# H0FR60.net
KiCad netlist of a schematic drawn in EAGLE
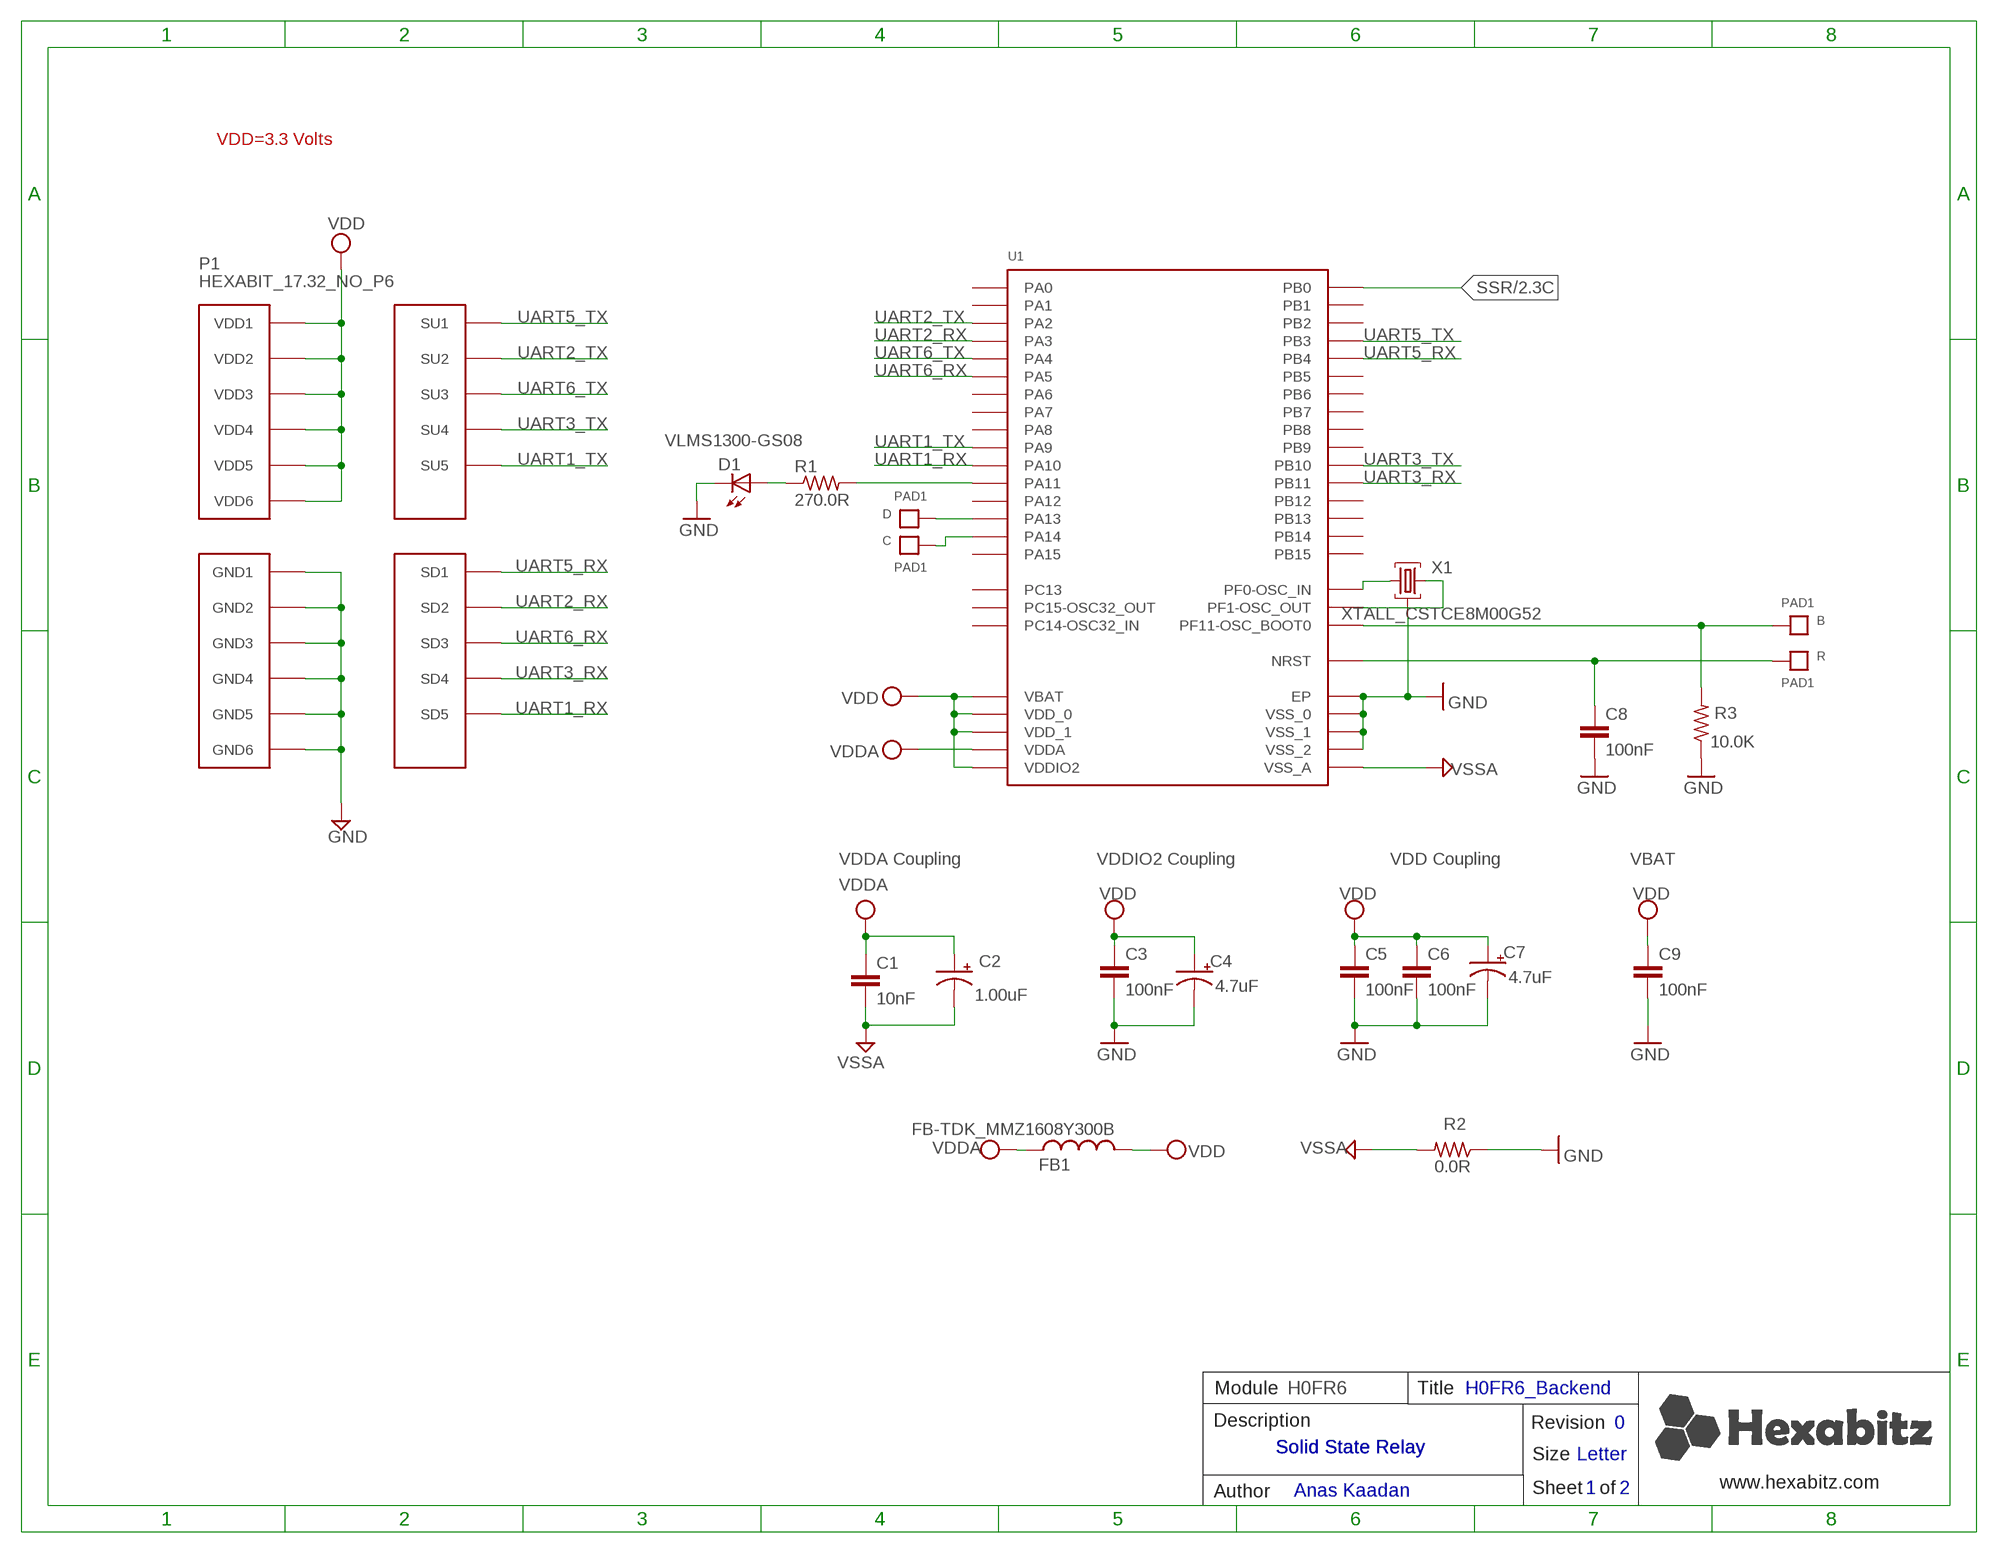
[diagram p0: schematic, sheet 1]
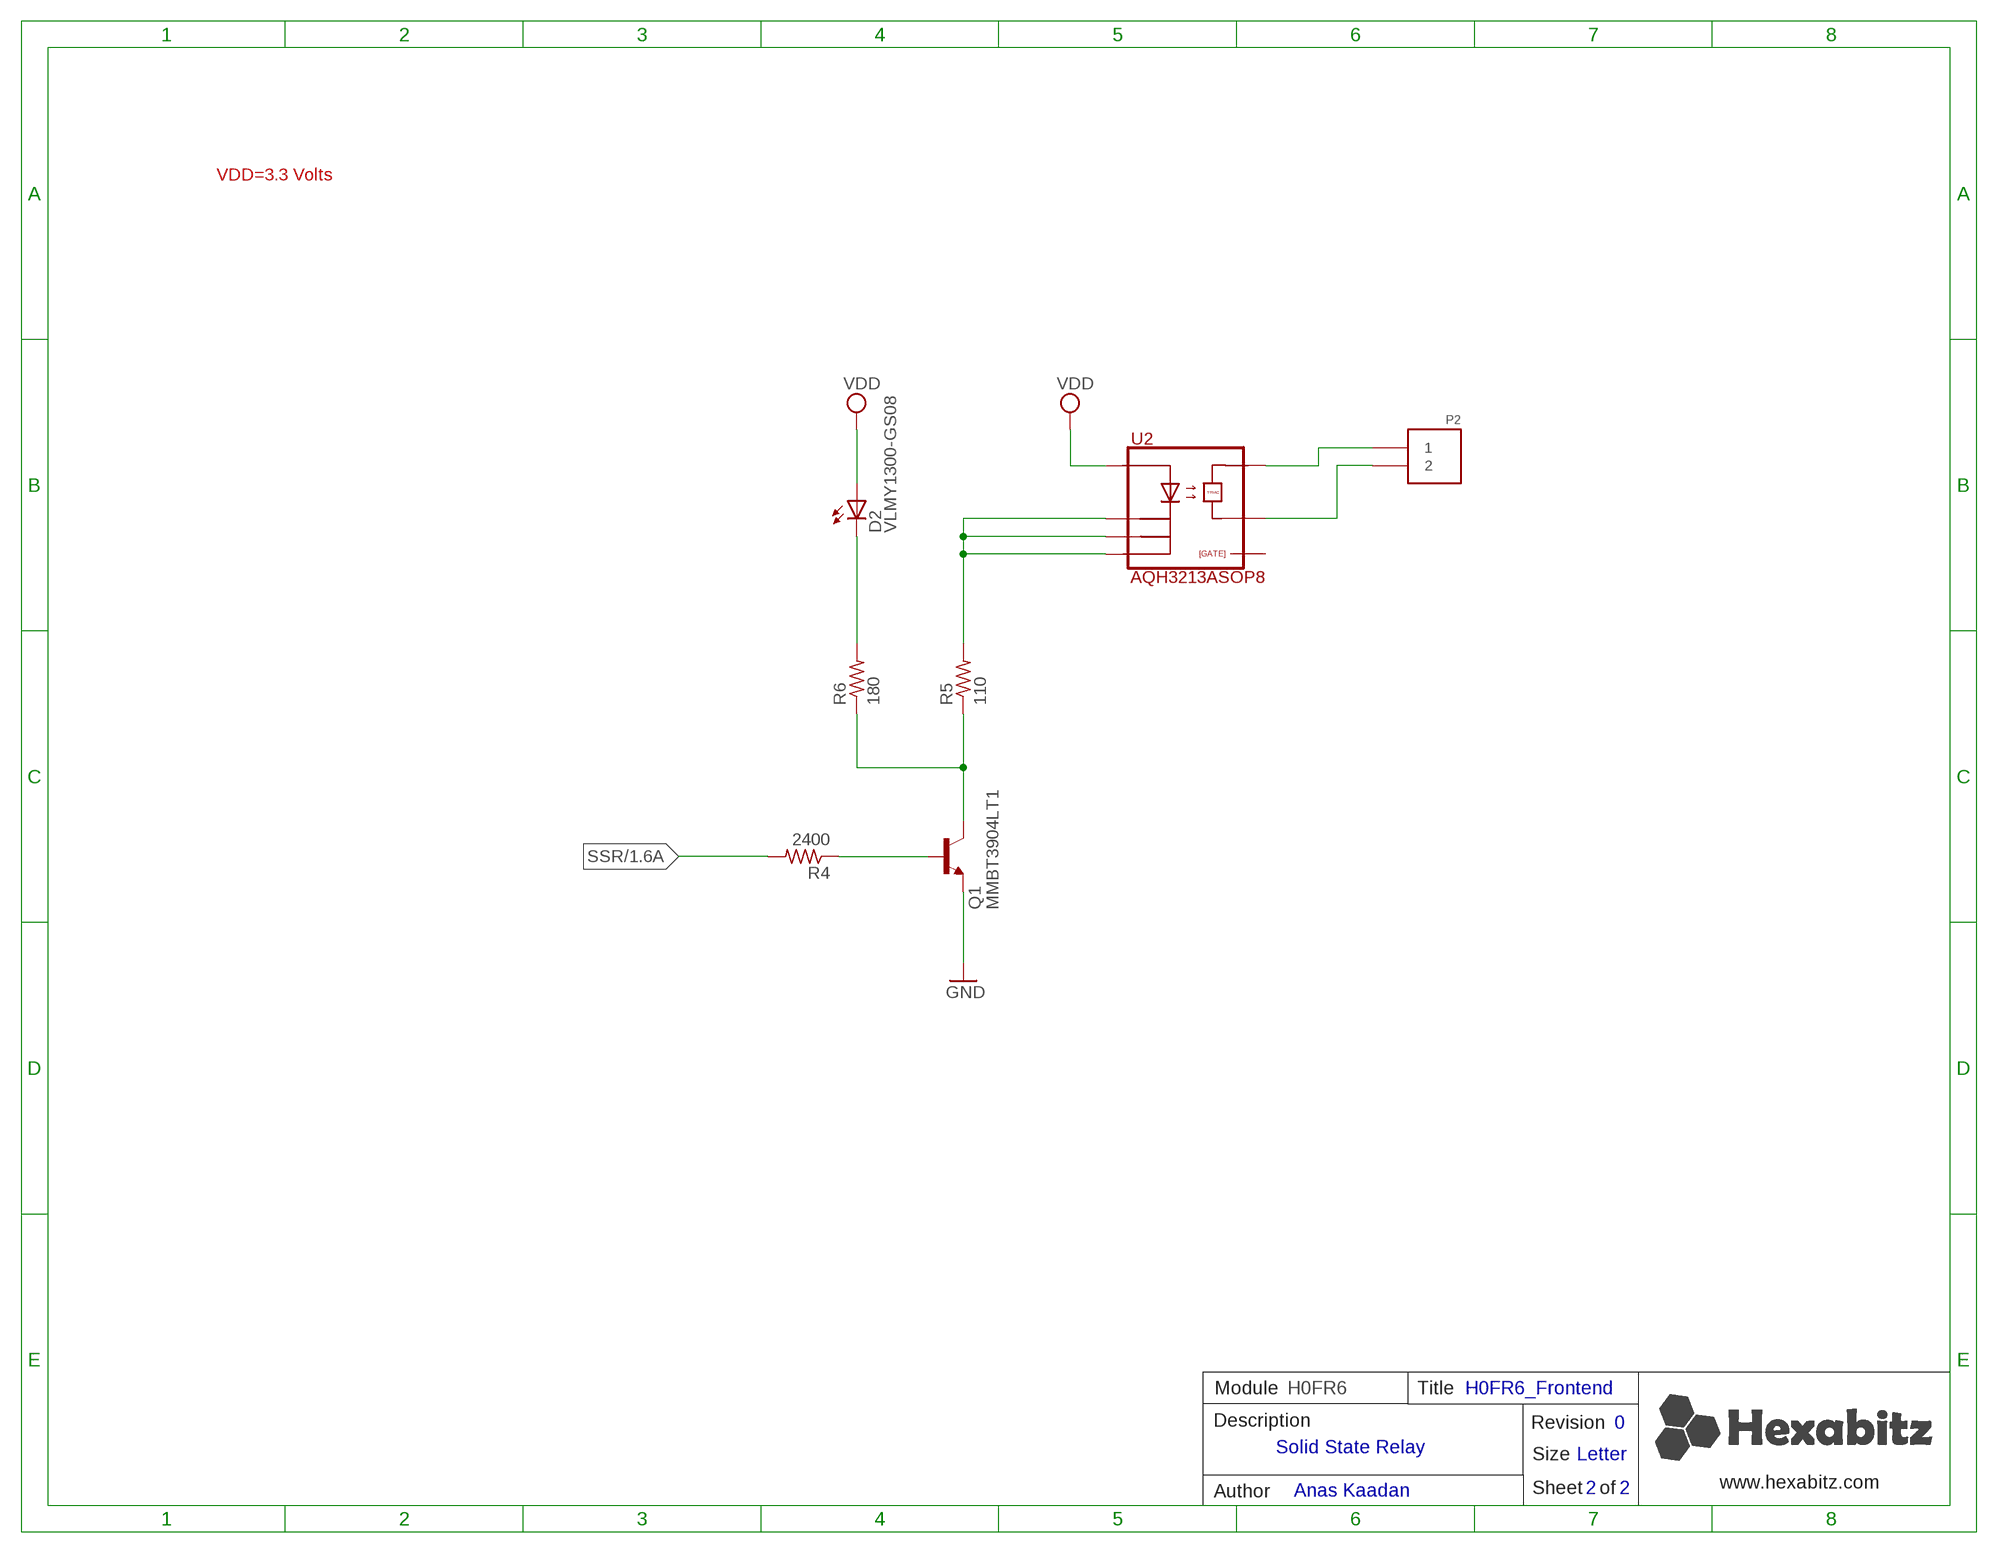
[diagram p1: schematic, sheet 2]

(export (version "E")
  (design (tool "Eeschema 10.0.6"))
  (components
    (comp (ref "B")
      (value "PAD1")
      (footprint "eagle-import:PAD1")
      (libsource (lib "eagle-import") (part "PAD1"))
    )
    (comp (ref "C")
      (value "PAD1")
      (footprint "eagle-import:PAD1")
      (libsource (lib "eagle-import") (part "PAD1"))
    )
    (comp (ref "C1")
      (value "10nF")
      (footprint "eagle-import:C-0603")
      (fields
        (field (name "CAPACITANCE") "10nF")
        (field (name "MFN") "KEMET")
        (field (name "MPN") "C0603C103K5RACTU")
        (field (name "OCTOPART_URL") "https://octopart.com/c0603c103k5ractu-kemet-133094?r=sp&s=R_iPBxLnSmGqhkU2rIMFpg")
        (field (name "TOLERANCE") "10%")
        (field (name "VOLTAGE_RATING") "50V")
      )
      (libsource (lib "eagle-import") (part "C-0603"))
    )
    (comp (ref "C2")
      (value "1.00uF")
      (footprint "eagle-import:C-0805-POL")
      (fields
        (field (name "CAPACITANCE") "1.00uF")
        (field (name "MFN") "Yageo")
        (field (name "MPN") "CC0805KKX7R7BB105")
        (field (name "OCTOPART_URL") "https://octopart.com/cc0805kkx7r7bb105-yageo-8376555?r=sp&s=YKl1wwtkROau_X5nniH2ig")
        (field (name "TOLERANCE") "10%")
        (field (name "VOLTAGE_RATING") "16V")
      )
      (libsource (lib "eagle-import") (part "C-0805-POL"))
    )
    (comp (ref "C3")
      (value "100nF")
      (footprint "eagle-import:C-0603")
      (fields
        (field (name "CAPACITANCE") "100nF")
        (field (name "MFN") "KEMET")
        (field (name "MPN") "C0603C104K8RACTU")
        (field (name "OCTOPART_URL") "https://octopart.com/c0603c104k8ractu-kemet-145075?r=sp&s=9bS9ASSwSEqMCE9KBEQZ0g")
        (field (name "TOLERANCE") "10%")
        (field (name "VOLTAGE_RATING") "10V")
      )
      (libsource (lib "eagle-import") (part "C-0603"))
    )
    (comp (ref "C4")
      (value "4.7uF")
      (footprint "eagle-import:C-0805-POL")
      (fields
        (field (name "CAPACITANCE") "4.7uF")
        (field (name "MFN") "Murata")
        (field (name "MPN") "GRM21BC81E475KA12L")
        (field (name "OCTOPART_URL") "https://octopart.com/grm21bc81e475ka12l-murata-10331911?r=sp&s=RY3qZSD8T6mG6TC9CHI5qQ")
        (field (name "TOLERANCE") "10%")
        (field (name "VOLTAGE_RATING") "25V")
      )
      (libsource (lib "eagle-import") (part "C-0805-POL"))
    )
    (comp (ref "C5")
      (value "100nF")
      (footprint "eagle-import:C-0603")
      (fields
        (field (name "CAPACITANCE") "100nF")
        (field (name "MFN") "KEMET")
        (field (name "MPN") "C0603C104K8RACTU")
        (field (name "OCTOPART_URL") "https://octopart.com/c0603c104k8ractu-kemet-145075?r=sp&s=9bS9ASSwSEqMCE9KBEQZ0g")
        (field (name "TOLERANCE") "10%")
        (field (name "VOLTAGE_RATING") "10")
      )
      (libsource (lib "eagle-import") (part "C-0603"))
    )
    (comp (ref "C6")
      (value "100nF")
      (footprint "eagle-import:C-0603")
      (fields
        (field (name "CAPACITANCE") "100nF")
        (field (name "MFN") "KEMET")
        (field (name "MPN") "C0603C104K8RACTU")
        (field (name "OCTOPART_URL") "https://octopart.com/c0603c104k8ractu-kemet-145075?r=sp&s=9bS9ASSwSEqMCE9KBEQZ0g")
        (field (name "TOLERANCE") "10%")
        (field (name "VOLTAGE_RATING") "10V")
      )
      (libsource (lib "eagle-import") (part "C-0603"))
    )
    (comp (ref "C7")
      (value "4.7uF")
      (footprint "eagle-import:C-0805-POL")
      (fields
        (field (name "CAPACITANCE") "4.7uF")
        (field (name "MFN") "Murata")
        (field (name "MPN") "GRM21BC81E475KA12L")
        (field (name "OCTOPART_URL") "https://octopart.com/grm21bc81e475ka12l-murata-10331911?r=sp&s=RY3qZSD8T6mG6TC9CHI5qQ")
        (field (name "TOLERANCE") "10%")
        (field (name "VOLTAGE_RATING") "25V")
      )
      (libsource (lib "eagle-import") (part "C-0805-POL"))
    )
    (comp (ref "C8")
      (value "100nF")
      (footprint "eagle-import:C-0603")
      (fields
        (field (name "CAPACITANCE") "100nF")
        (field (name "MFN") "KEMET")
        (field (name "MPN") "C0603C104K8RACTU")
        (field (name "OCTOPART_URL") "https://octopart.com/c0603c104k8ractu-kemet-145075?r=sp&s=9bS9ASSwSEqMCE9KBEQZ0g")
        (field (name "TOLERANCE") "10%")
        (field (name "VOLTAGE_RATING") "10V")
      )
      (libsource (lib "eagle-import") (part "C-0603"))
    )
    (comp (ref "C9")
      (value "100nF")
      (footprint "eagle-import:C-0603")
      (fields
        (field (name "CAPACITANCE") "100nF")
        (field (name "MFN") "KEMET")
        (field (name "MPN") "C0603C104K8RACTU")
        (field (name "OCTOPART_URL") "https://octopart.com/c0603c104k8ractu-kemet-145075?r=sp&s=9bS9ASSwSEqMCE9KBEQZ0g")
        (field (name "TOLERANCE") "10V")
        (field (name "VOLTAGE_RATING") "10%")
      )
      (libsource (lib "eagle-import") (part "C-0603"))
    )
    (comp (ref "D")
      (value "PAD1")
      (footprint "eagle-import:PAD1")
      (libsource (lib "eagle-import") (part "PAD1"))
    )
    (comp (ref "D1")
      (value "VLMS1300-GS08")
      (footprint "eagle-import:VLMS1300-GS08")
      (fields
        (field (name "MFN") "Vishay")
        (field (name "MPN") "VLMS1300-GS08")
        (field (name "OCTOPART_URL") "https://octopart.com/vlms1300-gs08-vishay-21709201?r=sp&s=_gcP4_q8T1SC6PJQPTQ9yA")
      )
      (libsource (lib "eagle-import") (part "VLMS1300-GS08"))
    )
    (comp (ref "FB1")
      (value "FB-TDK_MMZ1608Y300B")
      (footprint "eagle-import:FB-TDK_MMZ1608Y300B")
      (fields
        (field (name "MFN") "TDK ")
        (field (name "MPN") "MMZ1608Y300B")
        (field (name "OCTOPART_URL") "https://octopart.com/mmz1608y300b-tdk-368280?r=sp&s=cd9_2ZEqQ9q9UNBuQgHAiA")
      )
      (libsource (lib "eagle-import") (part "FB-TDK_MMZ1608Y300B"))
    )
    (comp (ref "P1")
      (value "HEXABIT_17.32_NO_P6")
      (footprint "eagle-import:HEXABIT_17.32_NO_P6")
      (libsource (lib "eagle-import") (part "HEXABIT_?_NO_P617.32"))
    )
    (comp (ref "R")
      (value "PAD1")
      (footprint "eagle-import:PAD1")
      (libsource (lib "eagle-import") (part "PAD1"))
    )
    (comp (ref "R1")
      (value "270.0R")
      (footprint "eagle-import:R-0603")
      (fields
        (field (name "MFN") "Yageo")
        (field (name "MPN") "RC0603FR-07270RL")
        (field (name "OCTOPART_URL") "https://octopart.com/search?q=RC0603FR-07270RL&start=0")
        (field (name "RESISTANCE") "270.0 Ohm")
        (field (name "TOLERANCE") "1%")
      )
      (libsource (lib "eagle-import") (part "R-0603"))
    )
    (comp (ref "R2")
      (value "0.0R")
      (footprint "eagle-import:R-0603")
      (fields
        (field (name "MFN") "Yageo")
        (field (name "MPN") "RC0603JR-070RL")
        (field (name "OCTOPART_URL") "https://octopart.com/rc0603jr-070rl-yageo-1241539?r=sp&s=X2NteqRjRNWrnx42Y0aliA")
        (field (name "RESISTANCE") "0.0 Ohm")
      )
      (libsource (lib "eagle-import") (part "R-0603"))
    )
    (comp (ref "R3")
      (value "10.0K")
      (footprint "eagle-import:R-0603")
      (fields
        (field (name "MFN") "Yageo")
        (field (name "MPN") "RC0603JR-0710KL")
        (field (name "OCTOPART_URL") "https://octopart.com/search?q=RC0603JR-0710KL&start=0")
        (field (name "RESISTANCE") "10.0K Ohm")
        (field (name "TOLERANCE") "5%")
      )
      (libsource (lib "eagle-import") (part "R-0603"))
    )
    (comp (ref "U1")
      (value "STM32F091CBU6")
      (footprint "eagle-import:STM32F091CBU6")
      (libsource (lib "eagle-import") (part "STM32F091CBU6"))
    )
    (comp (ref "X1")
      (value "XTALL_CSTCE8M00G52")
      (footprint "eagle-import:XTALL_CSTCE8M00G52")
      (fields (field (name "MPN") "CSTCE8M00G52Z-R0"))
      (libsource (lib "eagle-import") (part "XTALL_CSTCE8M00G52"))
    )
    (comp (ref "D2")
      (value "VLMY1300-GS08")
      (footprint "eagle-import:VLMS1300-GS08")
      (fields
        (field (name "MFN") "Vishay ")
        (field (name "MPN") "VLMY1300-GS08")
        (field (name "OCTOPART_URL") "https://octopart.com/vlmy1300-gs08-vishay-21709204")
      )
      (libsource (lib "eagle-import") (part "VLMS1300-GS08"))
    )
    (comp (ref "P2")
      (value "1546111-2")
      (footprint "eagle-import:1546111-2")
      (libsource (lib "eagle-import") (part "1546111-2"))
    )
    (comp (ref "Q1")
      (value "MMBT3904LT1")
      (footprint "eagle-import:MMBT3904LT1")
      (fields
        (field (name "MFN") "ON Semiconductor")
        (field (name "MPN") "MMBT3904LT1G")
        (field (name "OCTOPART_ID") "0bb6c2bc2200d471")
        (field (name "OCTOPART_URL") "http://octopart.com/mmbt3904lt1g-on+semiconductor-3280")
        (field (name "POLARITY") "NPN")
        (field (name "POWER_DISSIPATION") "0.225 W")
        (field (name "VOLTAGE_RATING_DC") "40.0 V")
      )
      (libsource (lib "eagle-import") (part "MMBT3904LT1"))
    )
    (comp (ref "R4")
      (value "2400")
      (footprint "eagle-import:R-0603")
      (fields
        (field (name "MFN") "Yageo")
        (field (name "MPN") "RC0603JR-070RL")
        (field (name "OCTOPART_URL") "https://octopart.com/crcw06032k40jnea-vishay-40298967")
        (field (name "RESISTANCE") "2400.0 Ω")
        (field (name "TOLERANCE") "±5%")
      )
      (libsource (lib "eagle-import") (part "R-0603"))
    )
    (comp (ref "R5")
      (value "110")
      (footprint "eagle-import:R-0603")
      (fields
        (field (name "MFN") "Yageo")
        (field (name "MPN") "RC0402FR-07100RL")
        (field (name "OCTOPART_URL") "https://octopart.com/crcw0603110rfkea-vishay-39455532")
        (field (name "RESISTANCE") "110.0 Ω")
        (field (name "TOLERANCE") "±1%")
      )
      (libsource (lib "eagle-import") (part "R-0603"))
    )
    (comp (ref "R6")
      (value "180")
      (footprint "eagle-import:R-0603")
      (fields
        (field (name "MFN") "Yageo")
        (field (name "MPN") "RC0402FR-07100RL")
        (field (name "OCTOPART_URL") "https://octopart.com/erj-3geyj181v-panasonic-55403673")
        (field (name "RESISTANCE") "180.0 Ω")
        (field (name "TOLERANCE") "±5%")
      )
      (libsource (lib "eagle-import") (part "R-0603"))
    )
    (comp (ref "U2")
      (value "AQH3213ASOP8")
      (footprint "eagle-import:AQH3213A")
      (fields
        (field (name "MFN") "Panasonic")
        (field (name "MPN") "AQH3213A")
        (field (name "OCTOPART_ID") "3c1df74ea8f7e3da")
        (field (name "OCTOPART_URL") "http://octopart.com/aqh3213a-panasonic-39432588")
        (field (name "OUTPUT_CURRENT") "1.2 A")
        (field (name "OUTPUT_VOLTAGE") "600.0 V")
      )
      (libsource (lib "eagle-import") (part "AQH3213ASOP8"))
    )
  )
  (nets
    (net (code "1") (name "GND") (class "Default")
      (node (ref "C3") (pin "2") (pinfunction "2_2") (pintype "passive"))
      (node (ref "C4") (pin "2") (pinfunction "-_2") (pintype "passive"))
      (node (ref "C5") (pin "2") (pinfunction "2_2") (pintype "passive"))
      (node (ref "C6") (pin "2") (pinfunction "2_2") (pintype "passive"))
      (node (ref "C7") (pin "2") (pinfunction "-_2") (pintype "passive"))
      (node (ref "C8") (pin "2") (pinfunction "2_2") (pintype "passive"))
      (node (ref "C9") (pin "2") (pinfunction "2_2") (pintype "passive"))
      (node (ref "D1") (pin "C") (pinfunction "C_C") (pintype "passive"))
      (node (ref "P1") (pin "PAD_PD10") (pinfunction "GND4_PAD_PD10") (pintype "power_in"))
      (node (ref "P1") (pin "PAD_PD11") (pinfunction "GND5_PAD_PD11") (pintype "power_in"))
      (node (ref "P1") (pin "PAD_PD12") (pinfunction "GND6_PAD_PD12") (pintype "power_in"))
      (node (ref "P1") (pin "PAD_PD7") (pinfunction "GND1_PAD_PD7") (pintype "power_in"))
      (node (ref "P1") (pin "PAD_PD8") (pinfunction "GND2_PAD_PD8") (pintype "power_in"))
      (node (ref "P1") (pin "PAD_PD9") (pinfunction "GND3_PAD_PD9") (pintype "power_in"))
      (node (ref "Q1") (pin "2") (pinfunction "E_2") (pintype "passive"))
      (node (ref "R2") (pin "1") (pinfunction "1_1") (pintype "passive"))
      (node (ref "R3") (pin "1") (pinfunction "1_1") (pintype "passive"))
      (node (ref "U1") (pin "EP") (pinfunction "EP_EP") (pintype "power_in"))
      (node (ref "U1") (pin "P$23") (pinfunction "VSS_0_P$23") (pintype "power_in"))
      (node (ref "U1") (pin "P$35") (pinfunction "VSS_1_P$35") (pintype "power_in"))
      (node (ref "U1") (pin "P$47") (pinfunction "VSS_2_P$47") (pintype "power_in"))
      (node (ref "X1") (pin "P$2") (pinfunction "2_P$2") (pintype "passive"))
    )
    (net (code "2") (name "Net-(D1-PadA)") (class "Default")
      (node (ref "D1") (pin "A") (pinfunction "A_A") (pintype "passive"))
      (node (ref "R1") (pin "1") (pinfunction "1_1") (pintype "passive"))
    )
    (net (code "3") (name "Net-(D2-PadC)") (class "Default")
      (node (ref "D2") (pin "C") (pinfunction "C_C") (pintype "passive"))
      (node (ref "R6") (pin "2") (pinfunction "2_2") (pintype "passive"))
    )
    (net (code "4") (name "Net-(Q1-B)") (class "Default")
      (node (ref "Q1") (pin "1") (pinfunction "B_1") (pintype "passive"))
      (node (ref "R4") (pin "1") (pinfunction "1_1") (pintype "passive"))
    )
    (net (code "5") (name "Net-(Q1-C)") (class "Default")
      (node (ref "Q1") (pin "3") (pinfunction "C_3") (pintype "passive"))
      (node (ref "R5") (pin "1") (pinfunction "1_1") (pintype "passive"))
      (node (ref "R6") (pin "1") (pinfunction "1_1") (pintype "passive"))
    )
    (net (code "6") (name "Net-(U1-NRST)") (class "Default")
      (node (ref "C8") (pin "1") (pinfunction "1_1") (pintype "passive"))
      (node (ref "R") (pin "P$1") (pinfunction "P$1_P$1") (pintype "passive"))
      (node (ref "R") (pin "P$2") (pinfunction "P$1_P$2") (pintype "passive"))
      (node (ref "U1") (pin "P$7") (pinfunction "NRST_P$7") (pintype "passive"))
    )
    (net (code "7") (name "Net-(U1-PA11)") (class "Default")
      (node (ref "R1") (pin "2") (pinfunction "2_2") (pintype "passive"))
      (node (ref "U1") (pin "P$32") (pinfunction "PA11_P$32") (pintype "bidirectional"))
    )
    (net (code "8") (name "Net-(U1-PA13)") (class "Default")
      (node (ref "D") (pin "P$1") (pinfunction "P$1_P$1") (pintype "passive"))
      (node (ref "D") (pin "P$2") (pinfunction "P$1_P$2") (pintype "passive"))
      (node (ref "U1") (pin "P$34") (pinfunction "PA13_P$34") (pintype "bidirectional"))
    )
    (net (code "9") (name "Net-(U1-PA14)") (class "Default")
      (node (ref "C") (pin "P$1") (pinfunction "P$1_P$1") (pintype "passive"))
      (node (ref "C") (pin "P$2") (pinfunction "P$1_P$2") (pintype "passive"))
      (node (ref "U1") (pin "P$37") (pinfunction "PA14_P$37") (pintype "bidirectional"))
    )
    (net (code "10") (name "Net-(U1-PF0-OSC_IN)") (class "Default")
      (node (ref "U1") (pin "P$5") (pinfunction "PF0-OSC_IN_P$5") (pintype "bidirectional"))
      (node (ref "X1") (pin "P$1") (pinfunction "1_P$1") (pintype "passive"))
    )
    (net (code "11") (name "Net-(U1-PF1-OSC_OUT)") (class "Default")
      (node (ref "U1") (pin "P$6") (pinfunction "PF1-OSC_OUT_P$6") (pintype "bidirectional"))
      (node (ref "X1") (pin "P$3") (pinfunction "3_P$3") (pintype "passive"))
    )
    (net (code "12") (name "Net-(U1-PF11-OSC_BOOT0)") (class "Default")
      (node (ref "B") (pin "P$1") (pinfunction "P$1_P$1") (pintype "passive"))
      (node (ref "B") (pin "P$2") (pinfunction "P$1_P$2") (pintype "passive"))
      (node (ref "R3") (pin "2") (pinfunction "2_2") (pintype "passive"))
      (node (ref "U1") (pin "P$44") (pinfunction "PF11-OSC_BOOT0_P$44") (pintype "bidirectional"))
    )
    (net (code "13") (name "Net-(U2-1)") (class "Default")
      (node (ref "R5") (pin "2") (pinfunction "2_2") (pintype "passive"))
      (node (ref "U2") (pin "P$1") (pinfunction "1_P$1") (pintype "bidirectional"))
      (node (ref "U2") (pin "P$3") (pinfunction "3_P$3") (pintype "bidirectional"))
      (node (ref "U2") (pin "P$4") (pinfunction "4_P$4") (pintype "bidirectional"))
    )
    (net (code "14") (name "Net-(U2-6)") (class "Default")
      (node (ref "P2") (pin "2") (pinfunction "2_2") (pintype "power_in"))
      (node (ref "U2") (pin "P$6") (pinfunction "6_P$6") (pintype "bidirectional"))
    )
    (net (code "15") (name "Net-(U2-8)") (class "Default")
      (node (ref "P2") (pin "1") (pinfunction "1_1") (pintype "power_in"))
      (node (ref "U2") (pin "P$8") (pinfunction "8_P$8") (pintype "bidirectional"))
    )
    (net (code "16") (name "SSR") (class "Default")
      (node (ref "R4") (pin "2") (pinfunction "2_2") (pintype "passive"))
      (node (ref "U1") (pin "P$18") (pinfunction "PB0_P$18") (pintype "bidirectional"))
    )
    (net (code "17") (name "UART1_RX") (class "Default")
      (node (ref "P1") (pin "PAD_PD5") (pinfunction "SD5_PAD_PD5") (pintype "bidirectional"))
      (node (ref "U1") (pin "P$31") (pinfunction "PA10_P$31") (pintype "bidirectional"))
    )
    (net (code "18") (name "UART1_TX") (class "Default")
      (node (ref "P1") (pin "PAD_PU5") (pinfunction "SU5_PAD_PU5") (pintype "bidirectional"))
      (node (ref "U1") (pin "P$30") (pinfunction "PA9_P$30") (pintype "bidirectional"))
    )
    (net (code "19") (name "UART2_RX") (class "Default")
      (node (ref "P1") (pin "PAD_PD2") (pinfunction "SD2_PAD_PD2") (pintype "bidirectional"))
      (node (ref "U1") (pin "P$13") (pinfunction "PA3_P$13") (pintype "bidirectional"))
    )
    (net (code "20") (name "UART2_TX") (class "Default")
      (node (ref "P1") (pin "PAD_PU2") (pinfunction "SU2_PAD_PU2") (pintype "bidirectional"))
      (node (ref "U1") (pin "P$12") (pinfunction "PA2_P$12") (pintype "bidirectional"))
    )
    (net (code "21") (name "UART3_RX") (class "Default")
      (node (ref "P1") (pin "PAD_PD4") (pinfunction "SD4_PAD_PD4") (pintype "bidirectional"))
      (node (ref "U1") (pin "P$22") (pinfunction "PB11_P$22") (pintype "bidirectional"))
    )
    (net (code "22") (name "UART3_TX") (class "Default")
      (node (ref "P1") (pin "PAD_PU4") (pinfunction "SU4_PAD_PU4") (pintype "bidirectional"))
      (node (ref "U1") (pin "P$21") (pinfunction "PB10_P$21") (pintype "bidirectional"))
    )
    (net (code "23") (name "UART5_RX") (class "Default")
      (node (ref "P1") (pin "PAD_PD1") (pinfunction "SD1_PAD_PD1") (pintype "bidirectional"))
      (node (ref "U1") (pin "P$40") (pinfunction "PB4_P$40") (pintype "bidirectional"))
    )
    (net (code "24") (name "UART5_TX") (class "Default")
      (node (ref "P1") (pin "PAD_PU1") (pinfunction "SU1_PAD_PU1") (pintype "bidirectional"))
      (node (ref "U1") (pin "P$39") (pinfunction "PB3_P$39") (pintype "bidirectional"))
    )
    (net (code "25") (name "UART6_RX") (class "Default")
      (node (ref "P1") (pin "PAD_PD3") (pinfunction "SD3_PAD_PD3") (pintype "bidirectional"))
      (node (ref "U1") (pin "P$15") (pinfunction "PA5_P$15") (pintype "bidirectional"))
    )
    (net (code "26") (name "UART6_TX") (class "Default")
      (node (ref "P1") (pin "PAD_PU3") (pinfunction "SU3_PAD_PU3") (pintype "bidirectional"))
      (node (ref "U1") (pin "P$14") (pinfunction "PA4_P$14") (pintype "bidirectional"))
    )
    (net (code "27") (name "VDD") (class "Default")
      (node (ref "C3") (pin "1") (pinfunction "1_1") (pintype "passive"))
      (node (ref "C4") (pin "1") (pinfunction "+_1") (pintype "passive"))
      (node (ref "C5") (pin "1") (pinfunction "1_1") (pintype "passive"))
      (node (ref "C6") (pin "1") (pinfunction "1_1") (pintype "passive"))
      (node (ref "C7") (pin "1") (pinfunction "+_1") (pintype "passive"))
      (node (ref "C9") (pin "1") (pinfunction "1_1") (pintype "passive"))
      (node (ref "D2") (pin "A") (pinfunction "A_A") (pintype "passive"))
      (node (ref "FB1") (pin "2") (pinfunction "2_2") (pintype "passive"))
      (node (ref "P1") (pin "PAD_PU10") (pinfunction "VDD4_PAD_PU10") (pintype "power_in"))
      (node (ref "P1") (pin "PAD_PU11") (pinfunction "VDD5_PAD_PU11") (pintype "power_in"))
      (node (ref "P1") (pin "PAD_PU12") (pinfunction "VDD6_PAD_PU12") (pintype "power_in"))
      (node (ref "P1") (pin "PAD_PU7") (pinfunction "VDD1_PAD_PU7") (pintype "power_in"))
      (node (ref "P1") (pin "PAD_PU8") (pinfunction "VDD2_PAD_PU8") (pintype "power_in"))
      (node (ref "P1") (pin "PAD_PU9") (pinfunction "VDD3_PAD_PU9") (pintype "power_in"))
      (node (ref "U1") (pin "P$1") (pinfunction "VBAT_P$1") (pintype "power_in"))
      (node (ref "U1") (pin "P$24") (pinfunction "VDD_0_P$24") (pintype "power_in"))
      (node (ref "U1") (pin "P$36") (pinfunction "VDDIO2_P$36") (pintype "power_in"))
      (node (ref "U1") (pin "P$48") (pinfunction "VDD_1_P$48") (pintype "power_in"))
      (node (ref "U2") (pin "P$2") (pinfunction "2_P$2") (pintype "bidirectional"))
    )
    (net (code "28") (name "VDDA") (class "Default")
      (node (ref "C1") (pin "1") (pinfunction "1_1") (pintype "passive"))
      (node (ref "C2") (pin "1") (pinfunction "+_1") (pintype "passive"))
      (node (ref "FB1") (pin "1") (pinfunction "1_1") (pintype "passive"))
      (node (ref "U1") (pin "P$9") (pinfunction "VDDA_P$9") (pintype "power_in"))
    )
    (net (code "29") (name "VSSA") (class "Default")
      (node (ref "C1") (pin "2") (pinfunction "2_2") (pintype "passive"))
      (node (ref "C2") (pin "2") (pinfunction "-_2") (pintype "passive"))
      (node (ref "R2") (pin "2") (pinfunction "2_2") (pintype "passive"))
      (node (ref "U1") (pin "P$8") (pinfunction "VSS_A_P$8") (pintype "power_in"))
    )
    (net (code "30") (name "unconnected-(U1-PA0-PadP$10)") (class "Default")
      (node (ref "U1") (pin "P$10") (pinfunction "PA0_P$10") (pintype "bidirectional"))
    )
    (net (code "31") (name "unconnected-(U1-PA1-PadP$11)") (class "Default")
      (node (ref "U1") (pin "P$11") (pinfunction "PA1_P$11") (pintype "bidirectional"))
    )
    (net (code "32") (name "unconnected-(U1-PA6-PadP$16)") (class "Default")
      (node (ref "U1") (pin "P$16") (pinfunction "PA6_P$16") (pintype "bidirectional"))
    )
    (net (code "33") (name "unconnected-(U1-PA7-PadP$17)") (class "Default")
      (node (ref "U1") (pin "P$17") (pinfunction "PA7_P$17") (pintype "bidirectional"))
    )
    (net (code "34") (name "unconnected-(U1-PA8-PadP$29)") (class "Default")
      (node (ref "U1") (pin "P$29") (pinfunction "PA8_P$29") (pintype "bidirectional"))
    )
    (net (code "35") (name "unconnected-(U1-PA12-PadP$33)") (class "Default")
      (node (ref "U1") (pin "P$33") (pinfunction "PA12_P$33") (pintype "bidirectional"))
    )
    (net (code "36") (name "unconnected-(U1-PA15-PadP$38)") (class "Default")
      (node (ref "U1") (pin "P$38") (pinfunction "PA15_P$38") (pintype "bidirectional"))
    )
    (net (code "37") (name "unconnected-(U1-PB1-PadP$19)") (class "Default")
      (node (ref "U1") (pin "P$19") (pinfunction "PB1_P$19") (pintype "bidirectional"))
    )
    (net (code "38") (name "unconnected-(U1-PB2-PadP$20)") (class "Default")
      (node (ref "U1") (pin "P$20") (pinfunction "PB2_P$20") (pintype "bidirectional"))
    )
    (net (code "39") (name "unconnected-(U1-PB5-PadP$41)") (class "Default")
      (node (ref "U1") (pin "P$41") (pinfunction "PB5_P$41") (pintype "bidirectional"))
    )
    (net (code "40") (name "unconnected-(U1-PB6-PadP$42)") (class "Default")
      (node (ref "U1") (pin "P$42") (pinfunction "PB6_P$42") (pintype "bidirectional"))
    )
    (net (code "41") (name "unconnected-(U1-PB7-PadP$43)") (class "Default")
      (node (ref "U1") (pin "P$43") (pinfunction "PB7_P$43") (pintype "bidirectional"))
    )
    (net (code "42") (name "unconnected-(U1-PB8-PadP$45)") (class "Default")
      (node (ref "U1") (pin "P$45") (pinfunction "PB8_P$45") (pintype "bidirectional"))
    )
    (net (code "43") (name "unconnected-(U1-PB9-PadP$46)") (class "Default")
      (node (ref "U1") (pin "P$46") (pinfunction "PB9_P$46") (pintype "bidirectional"))
    )
    (net (code "44") (name "unconnected-(U1-PB12-PadP$25)") (class "Default")
      (node (ref "U1") (pin "P$25") (pinfunction "PB12_P$25") (pintype "bidirectional"))
    )
    (net (code "45") (name "unconnected-(U1-PB13-PadP$26)") (class "Default")
      (node (ref "U1") (pin "P$26") (pinfunction "PB13_P$26") (pintype "bidirectional"))
    )
    (net (code "46") (name "unconnected-(U1-PB14-PadP$27)") (class "Default")
      (node (ref "U1") (pin "P$27") (pinfunction "PB14_P$27") (pintype "bidirectional"))
    )
    (net (code "47") (name "unconnected-(U1-PB15-PadP$28)") (class "Default")
      (node (ref "U1") (pin "P$28") (pinfunction "PB15_P$28") (pintype "bidirectional"))
    )
    (net (code "48") (name "unconnected-(U1-PC13-PadP$2)") (class "Default")
      (node (ref "U1") (pin "P$2") (pinfunction "PC13_P$2") (pintype "bidirectional"))
    )
    (net (code "49") (name "unconnected-(U1-PC14-OSC32_IN-PadP$3)") (class "Default")
      (node (ref "U1") (pin "P$3") (pinfunction "PC14-OSC32_IN_P$3") (pintype "bidirectional"))
    )
    (net (code "50") (name "unconnected-(U1-PC15-OSC32_OUT-PadP$4)") (class "Default")
      (node (ref "U1") (pin "P$4") (pinfunction "PC15-OSC32_OUT_P$4") (pintype "bidirectional"))
    )
    (net (code "51") (name "unconnected-(U2-5-PadP$5)") (class "Default")
      (node (ref "U2") (pin "P$5") (pinfunction "5_P$5") (pintype "bidirectional"))
    )
  )
)
